# basic_Arduino.net
KiCad netlist of a schematic drawn in EAGLE
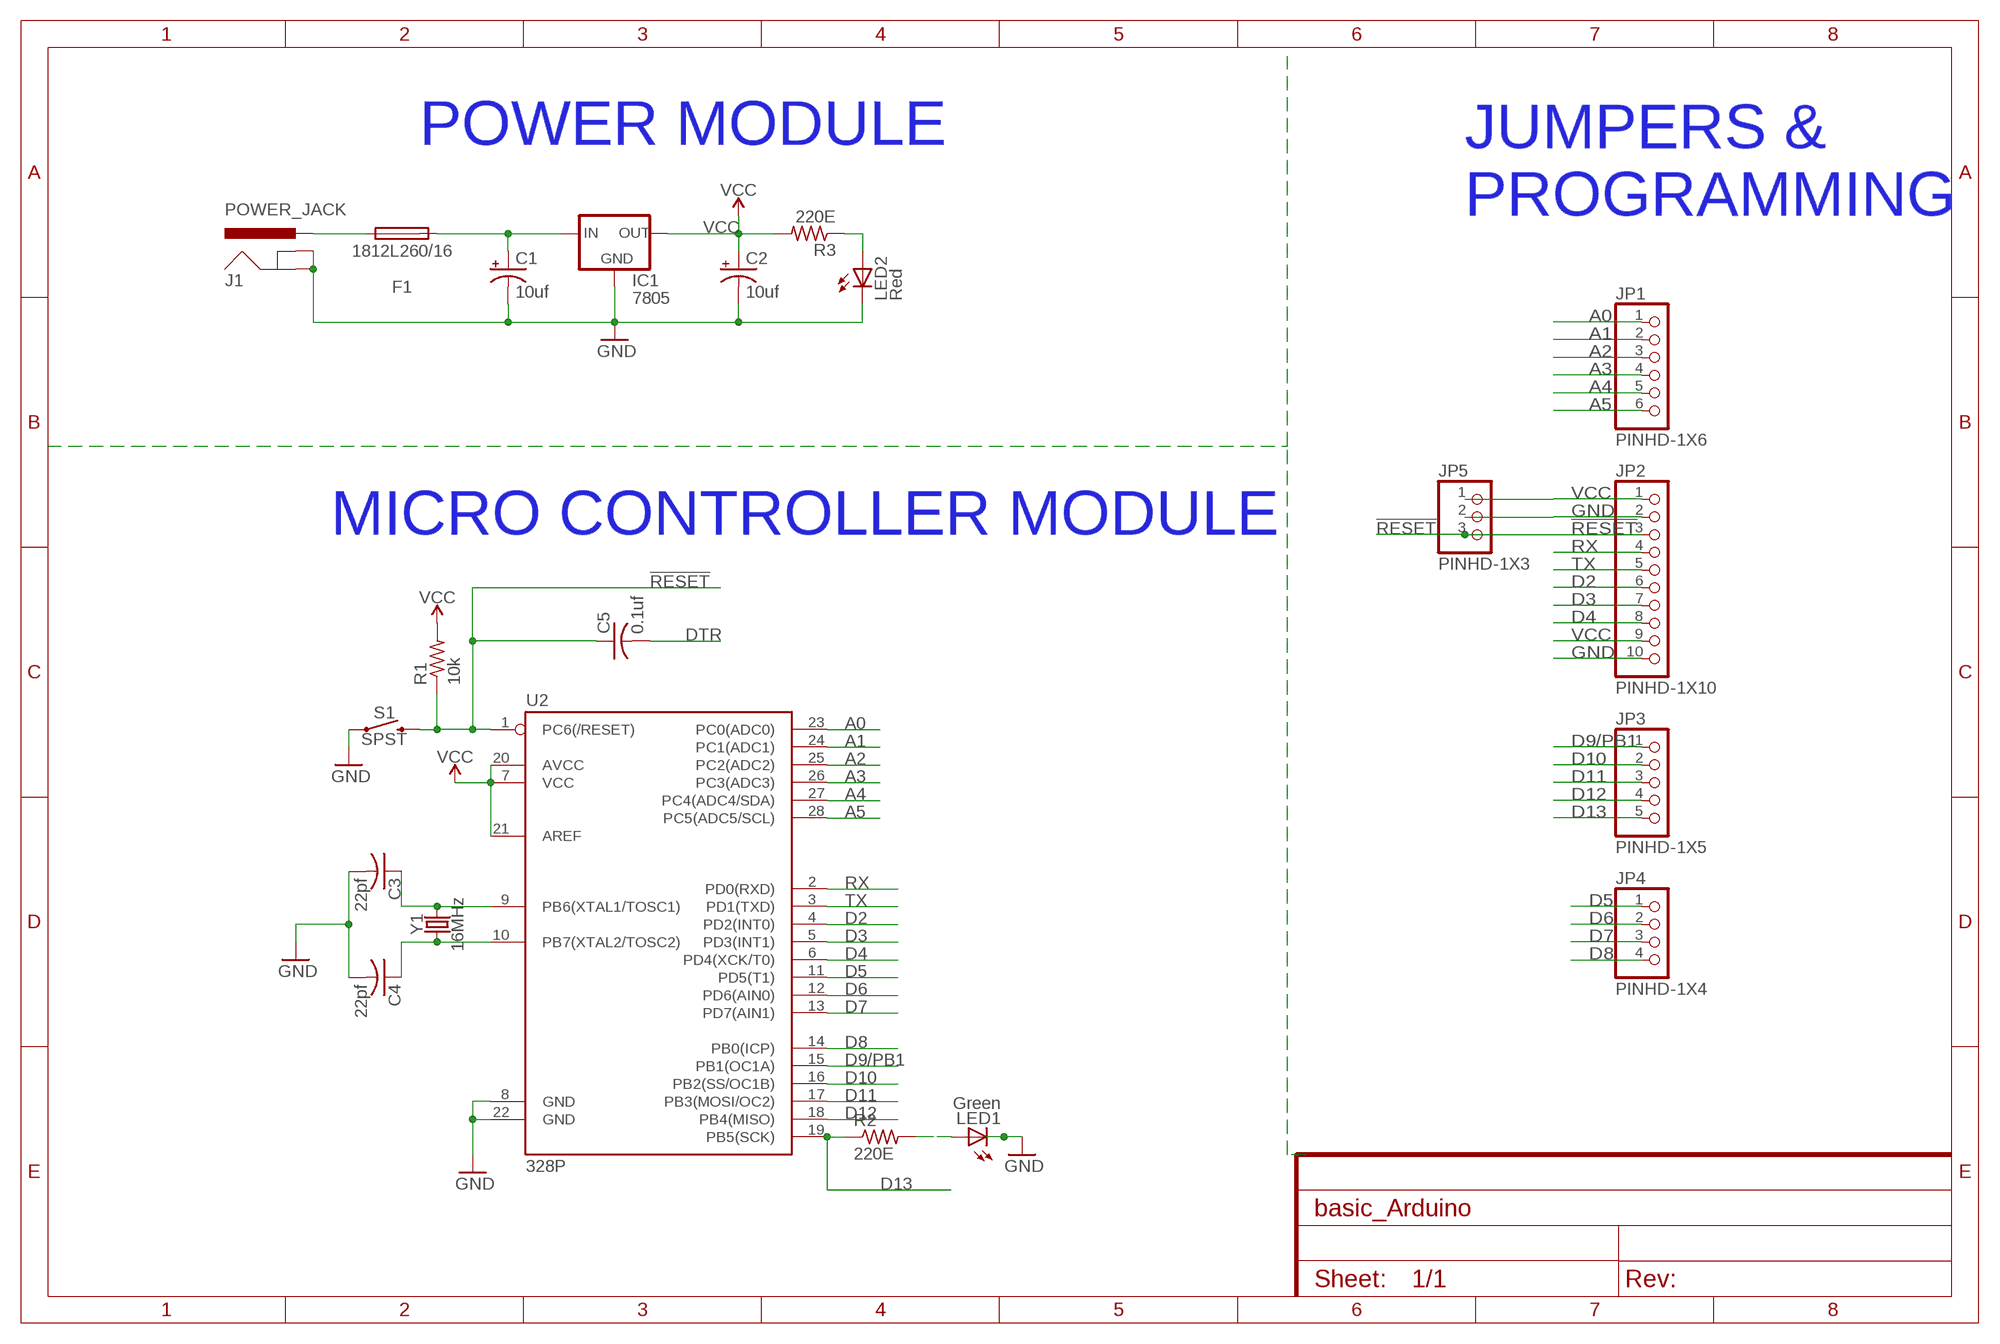
[diagram p0: schematic, sheet 1]

(export (version "E")
  (design (tool "Eeschema 10.0.6"))
  (components
    (comp (ref "C1")
      (value "10uf")
      (footprint "eagle-import:E2,5-6E")
      (libsource (lib "eagle-import") (part "CPOL-USE2,5-6E"))
    )
    (comp (ref "C2")
      (value "10uf")
      (footprint "eagle-import:E2,5-6E")
      (libsource (lib "eagle-import") (part "CPOL-USE2,5-6E"))
    )
    (comp (ref "C3")
      (value "22pf")
      (footprint "eagle-import:C025-024X044")
      (libsource (lib "eagle-import") (part "C-US025-024X044"))
    )
    (comp (ref "C4")
      (value "22pf")
      (footprint "eagle-import:C025-024X044")
      (libsource (lib "eagle-import") (part "C-US025-024X044"))
    )
    (comp (ref "C5")
      (value "0.1uf")
      (footprint "eagle-import:C025-024X044")
      (libsource (lib "eagle-import") (part "C-US025-024X044"))
    )
    (comp (ref "F1")
      (value "1812L260/16")
      (footprint "eagle-import:FUSC4532X125")
      (fields (field (name "MANUFACTURER") "Littlefuse") (field (name "MPN") "1812L260/12"))
      (libsource (lib "eagle-import") (part "1812L260/16"))
    )
    (comp (ref "IC1")
      (value "7805")
      (footprint "eagle-import:78XXS")
      (libsource (lib "eagle-import") (part "78XXS"))
    )
    (comp (ref "J1")
      (value "POWER_JACK")
      (footprint "eagle-import:POWER_JACK_PTH")
      (libsource (lib "eagle-import") (part "POWER_JACK"))
    )
    (comp (ref "JP1")
      (value "PINHD-1X6")
      (footprint "eagle-import:1X06")
      (libsource (lib "eagle-import") (part "PINHD-1X6"))
    )
    (comp (ref "JP2")
      (value "PINHD-1X10")
      (footprint "eagle-import:1X10")
      (libsource (lib "eagle-import") (part "PINHD-1X10"))
    )
    (comp (ref "JP3")
      (value "PINHD-1X5")
      (footprint "eagle-import:1X05")
      (libsource (lib "eagle-import") (part "PINHD-1X5"))
    )
    (comp (ref "JP4")
      (value "PINHD-1X4")
      (footprint "eagle-import:1X04")
      (libsource (lib "eagle-import") (part "PINHD-1X4"))
    )
    (comp (ref "JP5")
      (value "PINHD-1X3")
      (footprint "eagle-import:1X03")
      (libsource (lib "eagle-import") (part "PINHD-1X3"))
    )
    (comp (ref "LED1")
      (value "Green")
      (footprint "eagle-import:LED3MM")
      (libsource (lib "eagle-import") (part "LED3MM"))
    )
    (comp (ref "LED2")
      (value "Red")
      (footprint "eagle-import:LED3MM")
      (libsource (lib "eagle-import") (part "LED3MM"))
    )
    (comp (ref "R1")
      (value "10k")
      (footprint "eagle-import:0204_7")
      (libsource (lib "eagle-import") (part "R-US_0204/7"))
    )
    (comp (ref "R2")
      (value "220E")
      (footprint "eagle-import:0204_7")
      (libsource (lib "eagle-import") (part "R-US_0204/7"))
    )
    (comp (ref "R3")
      (value "220E")
      (footprint "eagle-import:0204_7")
      (libsource (lib "eagle-import") (part "R-US_0204/7"))
    )
    (comp (ref "S1")
      (value "SPST")
      (footprint "eagle-import:TACTILE_SWITCH_PTH_6.0MM")
      (libsource (lib "eagle-import") (part "MOMENTARY-SWITCH-SPST-PTH-6.0MM"))
    )
    (comp (ref "U2")
      (value "328P")
      (footprint "eagle-import:DIP28")
      (libsource (lib "eagle-import") (part "ATMEGA328P_PDIP"))
    )
    (comp (ref "Y1")
      (value "16MHz")
      (footprint "eagle-import:HC49US")
      (libsource (lib "eagle-import") (part "CRYSTAL-16MHZPTH-HC49US"))
    )
  )
  (nets
    (net (code "1") (name "/A0") (class "Default")
      (node (ref "JP1") (pin "1") (pinfunction "1_1") (pintype "passive"))
      (node (ref "U2") (pin "23") (pinfunction "PC0(ADC0)_23") (pintype "bidirectional"))
    )
    (net (code "2") (name "/A1") (class "Default")
      (node (ref "JP1") (pin "2") (pinfunction "2_2") (pintype "passive"))
      (node (ref "U2") (pin "24") (pinfunction "PC1(ADC1)_24") (pintype "bidirectional"))
    )
    (net (code "3") (name "/A2") (class "Default")
      (node (ref "JP1") (pin "3") (pinfunction "3_3") (pintype "passive"))
      (node (ref "U2") (pin "25") (pinfunction "PC2(ADC2)_25") (pintype "bidirectional"))
    )
    (net (code "4") (name "/A3") (class "Default")
      (node (ref "JP1") (pin "4") (pinfunction "4_4") (pintype "passive"))
      (node (ref "U2") (pin "26") (pinfunction "PC3(ADC3)_26") (pintype "bidirectional"))
    )
    (net (code "5") (name "/A4") (class "Default")
      (node (ref "JP1") (pin "5") (pinfunction "5_5") (pintype "passive"))
      (node (ref "U2") (pin "27") (pinfunction "PC4(ADC4/SDA)_27") (pintype "bidirectional"))
    )
    (net (code "6") (name "/A5") (class "Default")
      (node (ref "JP1") (pin "6") (pinfunction "6_6") (pintype "passive"))
      (node (ref "U2") (pin "28") (pinfunction "PC5(ADC5/SCL)_28") (pintype "bidirectional"))
    )
    (net (code "7") (name "/D2") (class "Default")
      (node (ref "JP2") (pin "6") (pinfunction "6_6") (pintype "passive"))
      (node (ref "U2") (pin "4") (pinfunction "PD2(INT0)_4") (pintype "bidirectional"))
    )
    (net (code "8") (name "/D3") (class "Default")
      (node (ref "JP2") (pin "7") (pinfunction "7_7") (pintype "passive"))
      (node (ref "U2") (pin "5") (pinfunction "PD3(INT1)_5") (pintype "bidirectional"))
    )
    (net (code "9") (name "/D4") (class "Default")
      (node (ref "JP2") (pin "8") (pinfunction "8_8") (pintype "passive"))
      (node (ref "U2") (pin "6") (pinfunction "PD4(XCK/T0)_6") (pintype "bidirectional"))
    )
    (net (code "10") (name "/D5") (class "Default")
      (node (ref "JP4") (pin "1") (pinfunction "1_1") (pintype "passive"))
      (node (ref "U2") (pin "11") (pinfunction "PD5(T1)_11") (pintype "bidirectional"))
    )
    (net (code "11") (name "/D6") (class "Default")
      (node (ref "JP4") (pin "2") (pinfunction "2_2") (pintype "passive"))
      (node (ref "U2") (pin "12") (pinfunction "PD6(AIN0)_12") (pintype "bidirectional"))
    )
    (net (code "12") (name "/D7") (class "Default")
      (node (ref "JP4") (pin "3") (pinfunction "3_3") (pintype "passive"))
      (node (ref "U2") (pin "13") (pinfunction "PD7(AIN1)_13") (pintype "bidirectional"))
    )
    (net (code "13") (name "/D8") (class "Default")
      (node (ref "JP4") (pin "4") (pinfunction "4_4") (pintype "passive"))
      (node (ref "U2") (pin "14") (pinfunction "PB0(ICP)_14") (pintype "bidirectional"))
    )
    (net (code "14") (name "/D9{slash}PB1") (class "Default")
      (node (ref "JP3") (pin "1") (pinfunction "1_1") (pintype "passive"))
      (node (ref "U2") (pin "15") (pinfunction "PB1(OC1A)_15") (pintype "bidirectional"))
    )
    (net (code "15") (name "/D10") (class "Default")
      (node (ref "JP3") (pin "2") (pinfunction "2_2") (pintype "passive"))
      (node (ref "U2") (pin "16") (pinfunction "PB2(SS/OC1B)_16") (pintype "bidirectional"))
    )
    (net (code "16") (name "/D11") (class "Default")
      (node (ref "JP3") (pin "3") (pinfunction "3_3") (pintype "passive"))
      (node (ref "U2") (pin "17") (pinfunction "PB3(MOSI/OC2)_17") (pintype "bidirectional"))
    )
    (net (code "17") (name "/D12") (class "Default")
      (node (ref "JP3") (pin "4") (pinfunction "4_4") (pintype "passive"))
      (node (ref "U2") (pin "18") (pinfunction "PB4(MISO)_18") (pintype "bidirectional"))
    )
    (net (code "18") (name "/D13") (class "Default")
      (node (ref "JP3") (pin "5") (pinfunction "5_5") (pintype "passive"))
      (node (ref "R2") (pin "1") (pinfunction "1_1") (pintype "passive"))
      (node (ref "U2") (pin "19") (pinfunction "PB5(SCK)_19") (pintype "bidirectional"))
    )
    (net (code "19") (name "/DTR") (class "Default")
      (node (ref "C5") (pin "2") (pinfunction "2_2") (pintype "passive"))
    )
    (net (code "20") (name "/RX") (class "Default")
      (node (ref "JP2") (pin "4") (pinfunction "4_4") (pintype "passive"))
      (node (ref "U2") (pin "2") (pinfunction "PD0(RXD)_2") (pintype "bidirectional"))
    )
    (net (code "21") (name "/TX") (class "Default")
      (node (ref "JP2") (pin "5") (pinfunction "5_5") (pintype "passive"))
      (node (ref "U2") (pin "3") (pinfunction "PD1(TXD)_3") (pintype "bidirectional"))
    )
    (net (code "22") (name "/~{RESET}") (class "Default")
      (node (ref "C5") (pin "1") (pinfunction "1_1") (pintype "passive"))
      (node (ref "JP2") (pin "3") (pinfunction "3_3") (pintype "passive"))
      (node (ref "JP5") (pin "3") (pinfunction "3_3") (pintype "passive"))
      (node (ref "R1") (pin "1") (pinfunction "1_1") (pintype "passive"))
      (node (ref "S1") (pin "3") (pinfunction "2_3") (pintype "passive"))
      (node (ref "U2") (pin "1") (pinfunction "PC6(/RESET)_1") (pintype "bidirectional"))
    )
    (net (code "23") (name "GND") (class "Default")
      (node (ref "C1") (pin "-") (pinfunction "-_-") (pintype "passive"))
      (node (ref "C2") (pin "-") (pinfunction "-_-") (pintype "passive"))
      (node (ref "C3") (pin "2") (pinfunction "2_2") (pintype "passive"))
      (node (ref "C4") (pin "2") (pinfunction "2_2") (pintype "passive"))
      (node (ref "IC1") (pin "GND") (pinfunction "GND_GND") (pintype "input"))
      (node (ref "J1") (pin "GND") (pinfunction "GND_GND") (pintype "bidirectional"))
      (node (ref "J1") (pin "GNDBREAK") (pinfunction "GNDBREAK_GNDBREAK") (pintype "bidirectional"))
      (node (ref "JP2") (pin "10") (pinfunction "10_10") (pintype "passive"))
      (node (ref "JP2") (pin "2") (pinfunction "2_2") (pintype "passive"))
      (node (ref "JP5") (pin "2") (pinfunction "2_2") (pintype "passive"))
      (node (ref "LED1") (pin "K") (pinfunction "C_K") (pintype "passive"))
      (node (ref "LED2") (pin "K") (pinfunction "C_K") (pintype "passive"))
      (node (ref "S1") (pin "1") (pinfunction "1_1") (pintype "passive"))
      (node (ref "U2") (pin "22") (pinfunction "GND_22") (pintype "bidirectional"))
      (node (ref "U2") (pin "8") (pinfunction "GND_8") (pintype "bidirectional"))
    )
    (net (code "24") (name "Net-(C1-Pad+)") (class "Default")
      (node (ref "C1") (pin "+") (pinfunction "+_+") (pintype "passive"))
      (node (ref "F1") (pin "2") (pinfunction "2_2") (pintype "passive"))
      (node (ref "IC1") (pin "IN") (pinfunction "IN_IN") (pintype "input"))
    )
    (net (code "25") (name "Net-(F1-Pad1)") (class "Default")
      (node (ref "F1") (pin "1") (pinfunction "1_1") (pintype "passive"))
      (node (ref "J1") (pin "PWR") (pinfunction "PWR_PWR") (pintype "bidirectional"))
    )
    (net (code "26") (name "Net-(LED1-PadA)") (class "Default")
      (node (ref "LED1") (pin "A") (pinfunction "A_A") (pintype "passive"))
      (node (ref "R2") (pin "2") (pinfunction "2_2") (pintype "passive"))
    )
    (net (code "27") (name "Net-(LED2-PadA)") (class "Default")
      (node (ref "LED2") (pin "A") (pinfunction "A_A") (pintype "passive"))
      (node (ref "R3") (pin "1") (pinfunction "1_1") (pintype "passive"))
    )
    (net (code "28") (name "Net-(U2-PB6(XTAL1{slash}TOSC1))") (class "Default")
      (node (ref "C3") (pin "1") (pinfunction "1_1") (pintype "passive"))
      (node (ref "U2") (pin "9") (pinfunction "PB6(XTAL1/TOSC1)_9") (pintype "bidirectional"))
      (node (ref "Y1") (pin "2") (pinfunction "2_2") (pintype "passive"))
    )
    (net (code "29") (name "Net-(U2-PB7(XTAL2{slash}TOSC2))") (class "Default")
      (node (ref "C4") (pin "1") (pinfunction "1_1") (pintype "passive"))
      (node (ref "U2") (pin "10") (pinfunction "PB7(XTAL2/TOSC2)_10") (pintype "bidirectional"))
      (node (ref "Y1") (pin "1") (pinfunction "1_1") (pintype "passive"))
    )
    (net (code "30") (name "VCC") (class "Default")
      (node (ref "C2") (pin "+") (pinfunction "+_+") (pintype "passive"))
      (node (ref "IC1") (pin "OUT") (pinfunction "OUT_OUT") (pintype "passive"))
      (node (ref "JP2") (pin "1") (pinfunction "1_1") (pintype "passive"))
      (node (ref "JP2") (pin "9") (pinfunction "9_9") (pintype "passive"))
      (node (ref "JP5") (pin "1") (pinfunction "1_1") (pintype "passive"))
      (node (ref "R1") (pin "2") (pinfunction "2_2") (pintype "passive"))
      (node (ref "R3") (pin "2") (pinfunction "2_2") (pintype "passive"))
      (node (ref "U2") (pin "20") (pinfunction "AVCC_20") (pintype "bidirectional"))
      (node (ref "U2") (pin "21") (pinfunction "AREF_21") (pintype "bidirectional"))
      (node (ref "U2") (pin "7") (pinfunction "VCC_7") (pintype "bidirectional"))
    )
  )
)
